# TalkingTom_FINAL9.net
KiCad netlist of a schematic drawn in EAGLE
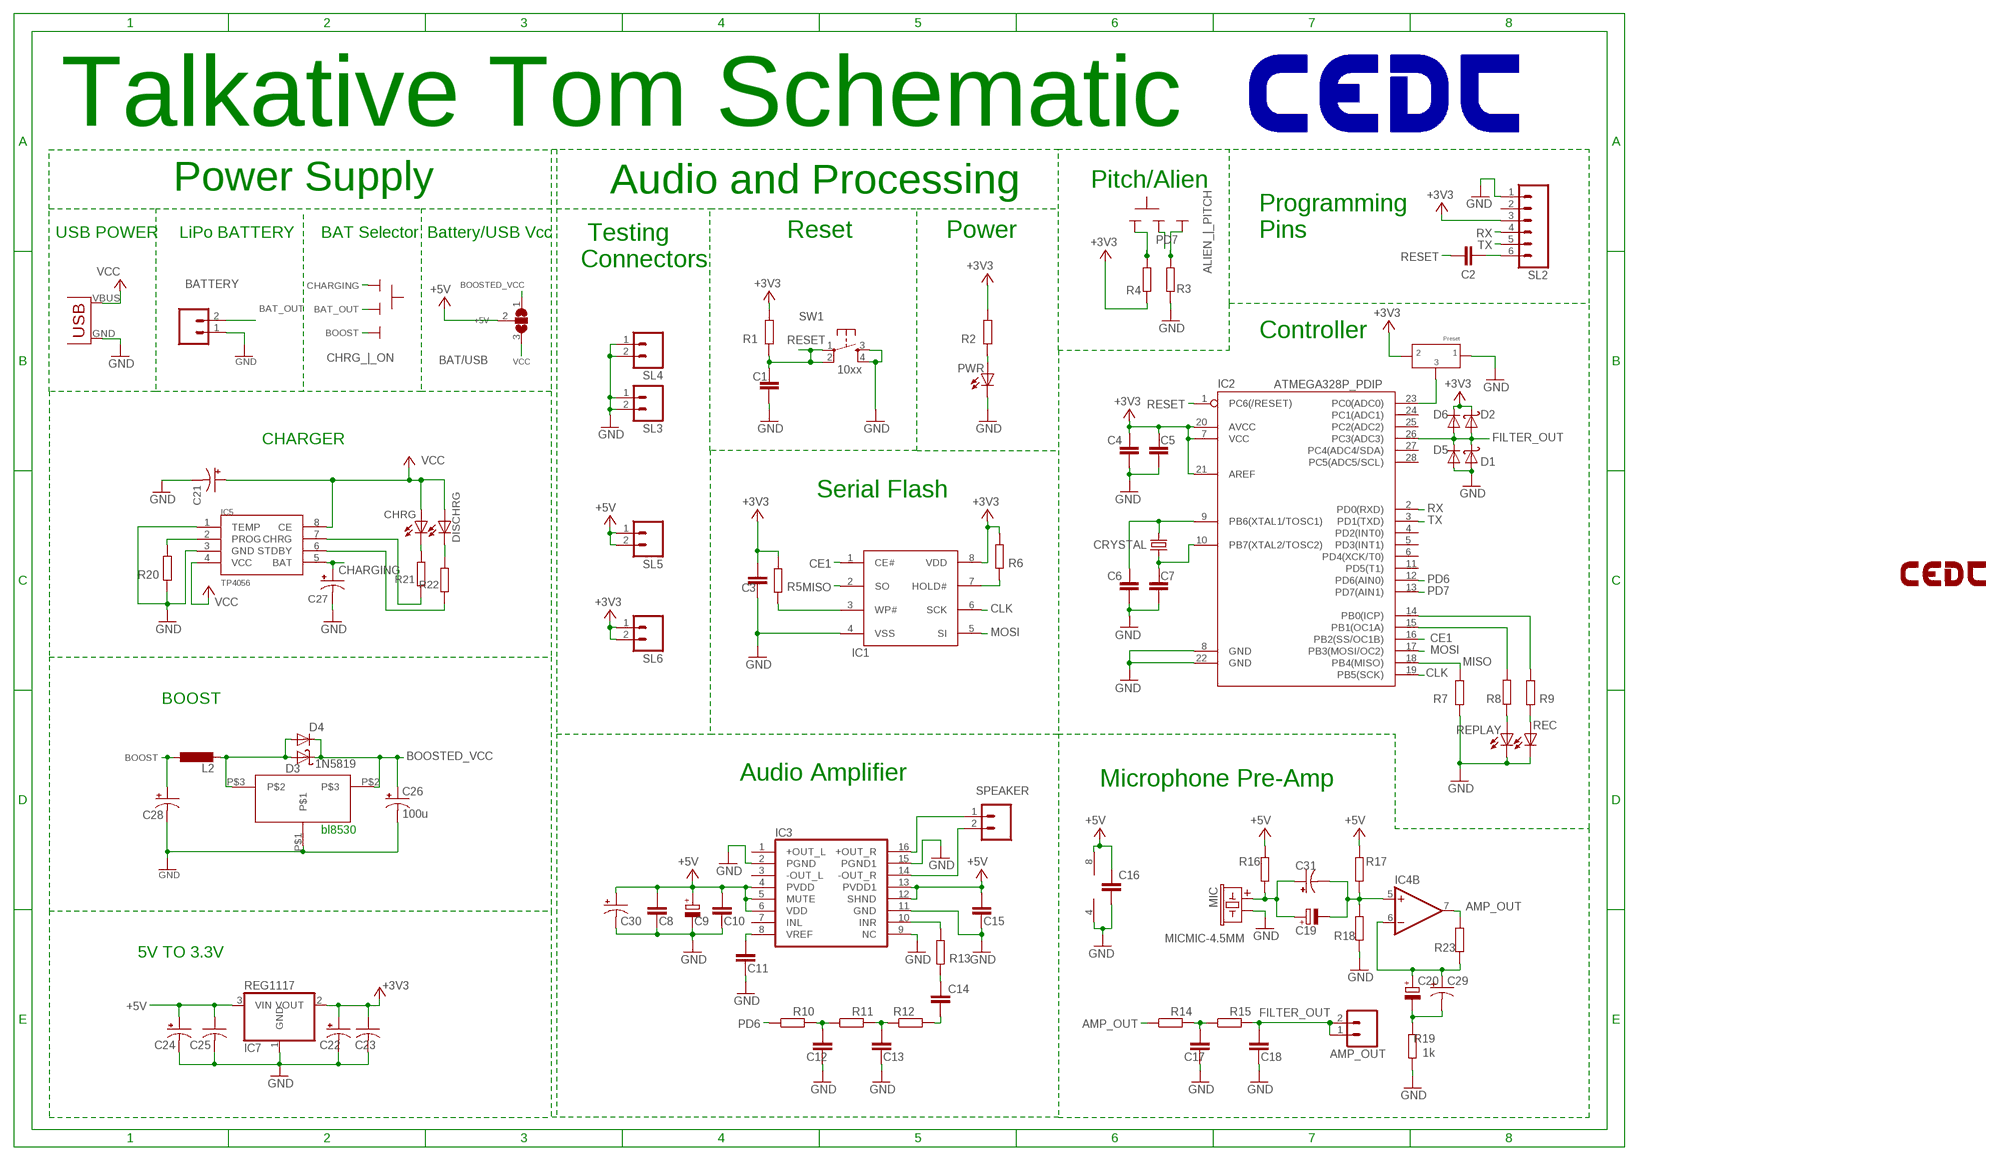
[diagram p0: schematic, sheet 1]

(export (version "E")
  (design (tool "Eeschema 10.0.6"))
  (components
    (comp (ref "ALIEN_|_PITCH")
      (value "SLIDESWITCH-BIG")
      (footprint "eagle-import:BIGSWITCH")
      (libsource (lib "eagle-import") (part "SLIDESWITCH-BIG"))
    )
    (comp (ref "AMP_OUT")
      (value "M02")
      (footprint "eagle-import:02P")
      (libsource (lib "eagle-import") (part "M02"))
    )
    (comp (ref "BAT/USB")
      (value "SJ2W")
      (footprint "eagle-import:SJ_2")
      (libsource (lib "eagle-import") (part "SJ2W"))
    )
    (comp (ref "BATTERY")
      (value "M02JST-PTH-2")
      (footprint "eagle-import:02P")
      (libsource (lib "eagle-import") (part "M02"))
    )
    (comp (ref "C1")
      (value "0.1u")
      (footprint "eagle-import:C0805")
      (libsource (lib "eagle-import") (part "rcl_C-EUC0805"))
    )
    (comp (ref "C2")
      (value "1uf")
      (footprint "eagle-import:C1206K")
      (libsource (lib "eagle-import") (part "rcl_C-EUC1206K"))
    )
    (comp (ref "C3")
      (value "0.1u")
      (footprint "eagle-import:C0805")
      (libsource (lib "eagle-import") (part "rcl_C-EUC0805"))
    )
    (comp (ref "C4")
      (value "0.1u")
      (footprint "eagle-import:C0805")
      (libsource (lib "eagle-import") (part "rcl_C-EUC0805"))
    )
    (comp (ref "C5")
      (value "0.1u")
      (footprint "eagle-import:C0805")
      (libsource (lib "eagle-import") (part "rcl_C-EUC0805"))
    )
    (comp (ref "C6")
      (value "22pf")
      (footprint "eagle-import:C0805")
      (libsource (lib "eagle-import") (part "rcl_C-EUC0805"))
    )
    (comp (ref "C7")
      (value "22pf")
      (footprint "eagle-import:C0805")
      (libsource (lib "eagle-import") (part "rcl_C-EUC0805"))
    )
    (comp (ref "C8")
      (value "1uf")
      (footprint "eagle-import:C1206")
      (libsource (lib "eagle-import") (part "rcl_C-EUC1206"))
    )
    (comp (ref "C9")
      (value "470uF")
      (footprint "eagle-import:E5-10,5")
      (libsource (lib "eagle-import") (part "resistor_CPOL-EUE5-10.5"))
    )
    (comp (ref "C10")
      (value "1uf")
      (footprint "eagle-import:C1206")
      (libsource (lib "eagle-import") (part "rcl_C-EUC1206"))
    )
    (comp (ref "C11")
      (value "0.1uf")
      (footprint "eagle-import:C1206")
      (libsource (lib "eagle-import") (part "rcl_C-EUC1206"))
    )
    (comp (ref "C12")
      (value "0.1u")
      (footprint "eagle-import:C0805")
      (libsource (lib "eagle-import") (part "C-EUC0805"))
    )
    (comp (ref "C13")
      (value "0.1uf")
      (footprint "eagle-import:C0805")
      (libsource (lib "eagle-import") (part "C-EUC0805"))
    )
    (comp (ref "C14")
      (value "0.47uF")
      (footprint "eagle-import:C0603")
      (libsource (lib "eagle-import") (part "rcl_C-EUC0603"))
    )
    (comp (ref "C15")
      (value "1uf")
      (footprint "eagle-import:C1206")
      (libsource (lib "eagle-import") (part "rcl_C-EUC1206"))
    )
    (comp (ref "C16")
      (value "0.1u")
      (footprint "eagle-import:C0805")
      (libsource (lib "eagle-import") (part "resistor_C-EUC0805"))
    )
    (comp (ref "C17")
      (value "0.1u")
      (footprint "eagle-import:C0805")
      (libsource (lib "eagle-import") (part "C-EUC0805"))
    )
    (comp (ref "C18")
      (value "0.1u")
      (footprint "eagle-import:C0805")
      (libsource (lib "eagle-import") (part "C-EUC0805"))
    )
    (comp (ref "C19")
      (value "10u")
      (footprint "eagle-import:E2,5-5")
      (libsource (lib "eagle-import") (part "CPOL-EUE2.5-5"))
    )
    (comp (ref "C20")
      (value "10u")
      (footprint "eagle-import:E2,5-5")
      (libsource (lib "eagle-import") (part "CPOL-EUE2.5-5"))
    )
    (comp (ref "C21")
      (value "10u")
      (footprint "eagle-import:C_6032-28R")
      (libsource (lib "eagle-import") (part "CEDT_JANUARY_2015_v7_CAP_POL_10V"))
    )
    (comp (ref "C22")
      (value "10u")
      (footprint "eagle-import:C_6032-28R")
      (libsource (lib "eagle-import") (part "CAP_POL_10V"))
    )
    (comp (ref "C23")
      (value "0.1u")
      (footprint "eagle-import:C0805")
      (libsource (lib "eagle-import") (part "CAP0805"))
    )
    (comp (ref "C24")
      (value "10u")
      (footprint "eagle-import:C_6032-28R")
      (libsource (lib "eagle-import") (part "CAP_POL_10V"))
    )
    (comp (ref "C25")
      (value "0.1u")
      (footprint "eagle-import:C0805")
      (libsource (lib "eagle-import") (part "CAP0805"))
    )
    (comp (ref "C26")
      (value "100u")
      (footprint "eagle-import:C_6032-28R")
      (libsource (lib "eagle-import") (part "CEDT_JANUARY_2015_v7_CAP_POL_10V"))
    )
    (comp (ref "C27")
      (value "10u")
      (footprint "eagle-import:C_6032-28R")
      (libsource (lib "eagle-import") (part "CAP_POL_10V"))
    )
    (comp (ref "C28")
      (value "10u")
      (footprint "eagle-import:C_6032-28R")
      (libsource (lib "eagle-import") (part "CAP_POL_10V"))
    )
    (comp (ref "C29")
      (value "10u")
      (footprint "eagle-import:C_6032-28R")
      (libsource (lib "eagle-import") (part "CEDT_JANUARY_2015_v7_CAP_POL_10V"))
    )
    (comp (ref "C30")
      (value "CAP_POL_10V")
      (footprint "eagle-import:C_6032-28R")
      (libsource (lib "eagle-import") (part "CEDT_SEPTEMBER_V2_CAP_POL_10V"))
    )
    (comp (ref "C31")
      (value "10u")
      (footprint "eagle-import:C_6032-28R")
      (libsource (lib "eagle-import") (part "CEDT_JANUARY_2015_v7_CAP_POL_10V"))
    )
    (comp (ref "CHRG")
      (value "LED3MM")
      (footprint "eagle-import:LED3MM")
      (libsource (lib "eagle-import") (part "adafruit_LED3MM"))
    )
    (comp (ref "CHRG_|_ON")
      (value "SLIDESWITCH-BIG")
      (footprint "eagle-import:BIGSWITCH")
      (libsource (lib "eagle-import") (part "SLIDESWITCH-BIG"))
    )
    (comp (ref "CRYSTAL")
      (value "16MHz")
      (footprint "eagle-import:HC49US")
      (libsource (lib "eagle-import") (part "CRYSTALHC49US"))
    )
    (comp (ref "D1")
      (value "1N5819")
      (footprint "eagle-import:DO41-10")
      (libsource (lib "eagle-import") (part "1N5819"))
    )
    (comp (ref "D2")
      (value "1N5819")
      (footprint "eagle-import:DO41-10")
      (libsource (lib "eagle-import") (part "1N5819"))
    )
    (comp (ref "D3")
      (value "1N5819")
      (footprint "eagle-import:DO41-10")
      (libsource (lib "eagle-import") (part "arduinodaya_v9_1N5819"))
    )
    (comp (ref "D4")
      (value "DIODE_DIODE-DO214AC")
      (footprint "eagle-import:DIODE_DO214AC")
      (libsource (lib "eagle-import") (part "DIODE_DIODE-DO214AC"))
    )
    (comp (ref "D5")
      (value "DIODE_DIODE-DO214AC")
      (footprint "eagle-import:DIODE_DO214AC")
      (libsource (lib "eagle-import") (part "DIODE_DIODE-DO214AC"))
    )
    (comp (ref "D6")
      (value "DIODE_DIODE-DO214AC")
      (footprint "eagle-import:DIODE_DO214AC")
      (libsource (lib "eagle-import") (part "DIODE_DIODE-DO214AC"))
    )
    (comp (ref "DISCHRG")
      (value "LED3MM")
      (footprint "eagle-import:LED3MM")
      (libsource (lib "eagle-import") (part "adafruit_LED3MM"))
    )
    (comp (ref "IC1")
      (value "SST25VF040B_SPI_FLASH")
      (footprint "eagle-import:SOIC08")
      (libsource (lib "eagle-import") (part "SST25VF040B_SPI_FLASH"))
    )
    (comp (ref "IC2")
      (value "ATMEGA328P_PDIP")
      (footprint "eagle-import:DIL28-3")
      (libsource (lib "eagle-import") (part "ATMEGA328P_PDIP"))
    )
    (comp (ref "IC3")
      (value "PAM8403")
      (footprint "eagle-import:SOP-16")
      (libsource (lib "eagle-import") (part "PAM8403"))
    )
    (comp (ref "IC4")
      (value "LM358N")
      (footprint "eagle-import:DIL08")
      (libsource (lib "eagle-import") (part "LM358N"))
    )
    (comp (ref "IC5")
      (value "TP4056")
      (footprint "eagle-import:SOP-8")
      (libsource (lib "eagle-import") (part "TP4056"))
    )
    (comp (ref "IC6")
      (value "BL8530_5V")
      (footprint "eagle-import:BL8530_5V")
      (libsource (lib "eagle-import") (part "BL8530_5V"))
    )
    (comp (ref "IC7")
      (value "REG1117")
      (footprint "eagle-import:SOT223")
      (libsource (lib "eagle-import") (part "REG1117"))
    )
    (comp (ref "L2")
      (value "47uH")
      (footprint "eagle-import:L5650M")
      (libsource (lib "eagle-import") (part "L-EUL5650M"))
    )
    (comp (ref "LOGO2")
      (value "LOGO-CEDTSILK-18MM")
      (footprint "eagle-import:LOGO-CEDT-SILK-18MM")
      (libsource (lib "eagle-import") (part "LOGO-CEDTSILK-18MM"))
    )
    (comp (ref "MIC")
      (value "MICMIC-4.5MM")
      (footprint "eagle-import:MIC-4.5MM")
      (libsource (lib "eagle-import") (part "MICMIC-4.5MM"))
    )
    (comp (ref "PWR")
      (value "LED3MM")
      (footprint "eagle-import:LED3MM")
      (libsource (lib "eagle-import") (part "LED3MM"))
    )
    (comp (ref "R1")
      (value "10k")
      (footprint "eagle-import:0204_7")
      (libsource (lib "eagle-import") (part "R-EU_0204/7"))
    )
    (comp (ref "R2")
      (value "1k")
      (footprint "eagle-import:0204_7")
      (libsource (lib "eagle-import") (part "R-EU_0204/7"))
    )
    (comp (ref "R3")
      (value "10k")
      (footprint "eagle-import:0204_7")
      (libsource (lib "eagle-import") (part "R-EU_0204/7"))
    )
    (comp (ref "R4")
      (value "10k")
      (footprint "eagle-import:0204_7")
      (libsource (lib "eagle-import") (part "R-EU_0204/7"))
    )
    (comp (ref "R5")
      (value "10k")
      (footprint "eagle-import:0204_7")
      (libsource (lib "eagle-import") (part "R-EU_0204/7"))
    )
    (comp (ref "R6")
      (value "10k")
      (footprint "eagle-import:0204_7")
      (libsource (lib "eagle-import") (part "R-EU_0204/7"))
    )
    (comp (ref "R7")
      (value "10k")
      (footprint "eagle-import:0204_7")
      (libsource (lib "eagle-import") (part "R-EU_0204/7"))
    )
    (comp (ref "R8")
      (value "1k")
      (footprint "eagle-import:0204_7")
      (libsource (lib "eagle-import") (part "R-EU_0204/7"))
    )
    (comp (ref "R9")
      (value "1k")
      (footprint "eagle-import:0204_7")
      (libsource (lib "eagle-import") (part "R-EU_0204/7"))
    )
    (comp (ref "R10")
      (value "330")
      (footprint "eagle-import:0204_7")
      (libsource (lib "eagle-import") (part "R-EU_0204/7"))
    )
    (comp (ref "R11")
      (value "330")
      (footprint "eagle-import:0204_7")
      (libsource (lib "eagle-import") (part "R-EU_0204/7"))
    )
    (comp (ref "R12")
      (value "R-EU_0204/7")
      (footprint "eagle-import:0204_7")
      (libsource (lib "eagle-import") (part "resistor_R-EU_0204/7"))
    )
    (comp (ref "R13")
      (value "10k")
      (footprint "eagle-import:0204_7")
      (libsource (lib "eagle-import") (part "resistor_R-EU_0204/7"))
    )
    (comp (ref "R14")
      (value "330")
      (footprint "eagle-import:0204_7")
      (libsource (lib "eagle-import") (part "R-EU_0204/7"))
    )
    (comp (ref "R15")
      (value "330")
      (footprint "eagle-import:0204_7")
      (libsource (lib "eagle-import") (part "R-EU_0204/7"))
    )
    (comp (ref "R16")
      (value "4.7k")
      (footprint "eagle-import:0204_7")
      (libsource (lib "eagle-import") (part "resistor_R-EU_0204/7"))
    )
    (comp (ref "R17")
      (value "10k")
      (footprint "eagle-import:0204_7")
      (libsource (lib "eagle-import") (part "resistor_R-EU_0204/7"))
    )
    (comp (ref "R18")
      (value "20k")
      (footprint "eagle-import:0204_7")
      (libsource (lib "eagle-import") (part "R-EU_0204/7"))
    )
    (comp (ref "R19")
      (value "1k")
      (footprint "eagle-import:0204_7")
      (libsource (lib "eagle-import") (part "resistor_R-EU_0204/7"))
    )
    (comp (ref "R20")
      (value "R-EU_0204/7")
      (footprint "eagle-import:0204_7")
      (libsource (lib "eagle-import") (part "R-EU_0204/7"))
    )
    (comp (ref "R21")
      (value "470")
      (footprint "eagle-import:0204_7")
      (libsource (lib "eagle-import") (part "R-EU_0204/7"))
    )
    (comp (ref "R22")
      (value "470")
      (footprint "eagle-import:0204_7")
      (libsource (lib "eagle-import") (part "R-EU_0204/7"))
    )
    (comp (ref "R23")
      (value "20k")
      (footprint "eagle-import:0204_7")
      (libsource (lib "eagle-import") (part "R-EU_0204/7"))
    )
    (comp (ref "REC")
      (value "LED3MM")
      (footprint "eagle-import:LED3MM")
      (libsource (lib "eagle-import") (part "LED3MM"))
    )
    (comp (ref "REPLAY")
      (value "LED3MM")
      (footprint "eagle-import:LED3MM")
      (libsource (lib "eagle-import") (part "LED3MM"))
    )
    (comp (ref "SL2")
      (value "M06")
      (footprint "eagle-import:06P")
      (libsource (lib "eagle-import") (part "M06"))
    )
    (comp (ref "SL3")
      (value "M02")
      (footprint "eagle-import:02P")
      (libsource (lib "eagle-import") (part "CEDT_JANUARY_2015_v7_M02"))
    )
    (comp (ref "SL4")
      (value "M02")
      (footprint "eagle-import:02P")
      (libsource (lib "eagle-import") (part "CEDT_JANUARY_2015_v7_M02"))
    )
    (comp (ref "SL5")
      (value "M02")
      (footprint "eagle-import:02P")
      (libsource (lib "eagle-import") (part "CEDT_JANUARY_2015_v7_M02"))
    )
    (comp (ref "SL6")
      (value "M02")
      (footprint "eagle-import:02P")
      (libsource (lib "eagle-import") (part "CEDT_JANUARY_2015_v7_M02"))
    )
    (comp (ref "SPEAKER")
      (value "M02JST-PTH-VERT")
      (footprint "eagle-import:02P")
      (libsource (lib "eagle-import") (part "M02"))
    )
    (comp (ref "SW1")
      (value "10xx")
      (footprint "eagle-import:B3F-10XX")
      (libsource (lib "eagle-import") (part "OMRON_SWITCH_10-XX"))
    )
    (comp (ref "TRIMPOT")
      (value "Preset")
      (footprint "eagle-import:PRESET-LR")
      (libsource (lib "eagle-import") (part "PRESET"))
    )
    (comp (ref "U$1")
      (value "USB(POWER)")
      (footprint "eagle-import:USB(POWER)")
      (libsource (lib "eagle-import") (part "USB(POWER)"))
    )
  )
  (nets
    (net (code "1") (name "+3V3") (class "Default")
      (node (ref "C22") (pin "+") (pinfunction "+_+") (pintype "passive"))
      (node (ref "C23") (pin "1") (pinfunction "1_1") (pintype "passive"))
      (node (ref "C3") (pin "1") (pinfunction "1_1") (pintype "passive"))
      (node (ref "C4") (pin "1") (pinfunction "1_1") (pintype "passive"))
      (node (ref "C5") (pin "1") (pinfunction "1_1") (pintype "passive"))
      (node (ref "D2") (pin "C") (pinfunction "C_C") (pintype "passive"))
      (node (ref "D6") (pin "C") (pinfunction "C_C") (pintype "passive"))
      (node (ref "IC1") (pin "8") (pinfunction "VDD_8") (pintype "passive"))
      (node (ref "IC2") (pin "20") (pinfunction "AVCC_20") (pintype "bidirectional"))
      (node (ref "IC2") (pin "21") (pinfunction "AREF_21") (pintype "bidirectional"))
      (node (ref "IC2") (pin "7") (pinfunction "VCC_7") (pintype "bidirectional"))
      (node (ref "IC7") (pin "2") (pinfunction "VOUT_2") (pintype "output"))
      (node (ref "R1") (pin "2") (pinfunction "2_2") (pintype "passive"))
      (node (ref "R2") (pin "2") (pinfunction "2_2") (pintype "passive"))
      (node (ref "R4") (pin "2") (pinfunction "2_2") (pintype "passive"))
      (node (ref "R5") (pin "1") (pinfunction "1_1") (pintype "passive"))
      (node (ref "R6") (pin "2") (pinfunction "2_2") (pintype "passive"))
      (node (ref "SL2") (pin "3") (pinfunction "3_3") (pintype "passive"))
      (node (ref "SL6") (pin "1") (pinfunction "1_1") (pintype "passive"))
      (node (ref "SL6") (pin "2") (pinfunction "2_2") (pintype "passive"))
      (node (ref "TRIMPOT") (pin "P$2") (pinfunction "2_P$2") (pintype "passive"))
    )
    (net (code "2") (name "+5V") (class "Default")
      (node (ref "BAT/USB") (pin "2") (pinfunction "2_2") (pintype "passive"))
      (node (ref "C10") (pin "2") (pinfunction "2_2") (pintype "passive"))
      (node (ref "C15") (pin "2") (pinfunction "2_2") (pintype "passive"))
      (node (ref "C16") (pin "1") (pinfunction "1_1") (pintype "passive"))
      (node (ref "C24") (pin "+") (pinfunction "+_+") (pintype "passive"))
      (node (ref "C25") (pin "1") (pinfunction "1_1") (pintype "passive"))
      (node (ref "C30") (pin "+") (pinfunction "+_+") (pintype "passive"))
      (node (ref "C8") (pin "1") (pinfunction "1_1") (pintype "passive"))
      (node (ref "C9") (pin "+") (pinfunction "+_+") (pintype "passive"))
      (node (ref "IC3") (pin "12") (pinfunction "SHND_12") (pintype "output"))
      (node (ref "IC3") (pin "13") (pinfunction "PVDD1_13") (pintype "output"))
      (node (ref "IC3") (pin "4") (pinfunction "PVDD_4") (pintype "input"))
      (node (ref "IC3") (pin "5") (pinfunction "MUTE_5") (pintype "input"))
      (node (ref "IC3") (pin "6") (pinfunction "VDD_6") (pintype "input"))
      (node (ref "IC4") (pin "8") (pinfunction "V+_8") (pintype "power_in"))
      (node (ref "IC7") (pin "3") (pinfunction "VIN_3") (pintype "input"))
      (node (ref "R16") (pin "2") (pinfunction "2_2") (pintype "passive"))
      (node (ref "R17") (pin "2") (pinfunction "2_2") (pintype "passive"))
      (node (ref "SL5") (pin "1") (pinfunction "1_1") (pintype "passive"))
      (node (ref "SL5") (pin "2") (pinfunction "2_2") (pintype "passive"))
    )
    (net (code "3") (name "/AMP_OUT") (class "Default")
      (node (ref "IC4") (pin "7") (pinfunction "OUT_7") (pintype "output"))
      (node (ref "R14") (pin "1") (pinfunction "1_1") (pintype "passive"))
      (node (ref "R23") (pin "2") (pinfunction "2_2") (pintype "passive"))
    )
    (net (code "4") (name "/BAT_OUT") (class "Default")
      (node (ref "BATTERY") (pin "2") (pinfunction "2_2") (pintype "passive"))
      (node (ref "CHRG_|_ON") (pin "2") (pinfunction "2_2") (pintype "bidirectional"))
    )
    (net (code "5") (name "/BOOST") (class "Default")
      (node (ref "C28") (pin "+") (pinfunction "+_+") (pintype "passive"))
      (node (ref "CHRG_|_ON") (pin "3") (pinfunction "3_3") (pintype "bidirectional"))
      (node (ref "L2") (pin "1") (pinfunction "1_1") (pintype "passive"))
    )
    (net (code "6") (name "/BOOSTED_VCC") (class "Default")
      (node (ref "BAT/USB") (pin "1") (pinfunction "1_1") (pintype "passive"))
      (node (ref "C26") (pin "+") (pinfunction "+_+") (pintype "passive"))
      (node (ref "D3") (pin "C") (pinfunction "C_C") (pintype "passive"))
      (node (ref "D4") (pin "C") (pinfunction "C_C") (pintype "passive"))
      (node (ref "IC6") (pin "P$2") (pinfunction "P$3_P$2") (pintype "bidirectional"))
    )
    (net (code "7") (name "/CE1") (class "Default")
      (node (ref "IC1") (pin "1") (pinfunction "CE#_1") (pintype "passive"))
      (node (ref "IC2") (pin "16") (pinfunction "PB2(SS/OC1B)_16") (pintype "bidirectional"))
    )
    (net (code "8") (name "/CHARGING") (class "Default")
      (node (ref "C27") (pin "+") (pinfunction "+_+") (pintype "passive"))
      (node (ref "CHRG_|_ON") (pin "1") (pinfunction "1_1") (pintype "bidirectional"))
      (node (ref "IC5") (pin "5") (pinfunction "BAT_5") (pintype "bidirectional"))
    )
    (net (code "9") (name "/CLK") (class "Default")
      (node (ref "IC1") (pin "6") (pinfunction "SCK_6") (pintype "passive"))
      (node (ref "IC2") (pin "19") (pinfunction "PB5(SCK)_19") (pintype "bidirectional"))
    )
    (net (code "10") (name "/FILTER_OUT") (class "Default")
      (node (ref "AMP_OUT") (pin "1") (pinfunction "1_1") (pintype "passive"))
      (node (ref "AMP_OUT") (pin "2") (pinfunction "2_2") (pintype "passive"))
      (node (ref "C18") (pin "1") (pinfunction "1_1") (pintype "passive"))
      (node (ref "D1") (pin "C") (pinfunction "C_C") (pintype "passive"))
      (node (ref "D2") (pin "A") (pinfunction "A_A") (pintype "passive"))
      (node (ref "D5") (pin "C") (pinfunction "C_C") (pintype "passive"))
      (node (ref "D6") (pin "A") (pinfunction "A_A") (pintype "passive"))
      (node (ref "IC2") (pin "26") (pinfunction "PC3(ADC3)_26") (pintype "bidirectional"))
      (node (ref "R15") (pin "2") (pinfunction "2_2") (pintype "passive"))
    )
    (net (code "11") (name "/MISO") (class "Default")
      (node (ref "IC1") (pin "2") (pinfunction "SO_2") (pintype "passive"))
      (node (ref "IC2") (pin "18") (pinfunction "PB4(MISO)_18") (pintype "bidirectional"))
      (node (ref "R7") (pin "1") (pinfunction "1_1") (pintype "passive"))
    )
    (net (code "12") (name "/MOSI") (class "Default")
      (node (ref "IC1") (pin "5") (pinfunction "SI_5") (pintype "passive"))
      (node (ref "IC2") (pin "17") (pinfunction "PB3(MOSI/OC2)_17") (pintype "bidirectional"))
    )
    (net (code "13") (name "/PD6") (class "Default")
      (node (ref "IC2") (pin "12") (pinfunction "PD6(AIN0)_12") (pintype "bidirectional"))
      (node (ref "R10") (pin "1") (pinfunction "1_1") (pintype "passive"))
    )
    (net (code "14") (name "/PD7") (class "Default")
      (node (ref "ALIEN_|_PITCH") (pin "2") (pinfunction "2_2") (pintype "bidirectional"))
      (node (ref "IC2") (pin "13") (pinfunction "PD7(AIN1)_13") (pintype "bidirectional"))
    )
    (net (code "15") (name "/RESET") (class "Default")
      (node (ref "C1") (pin "1") (pinfunction "1_1") (pintype "passive"))
      (node (ref "C2") (pin "2") (pinfunction "2_2") (pintype "passive"))
      (node (ref "IC2") (pin "1") (pinfunction "PC6(/RESET)_1") (pintype "bidirectional"))
      (node (ref "R1") (pin "1") (pinfunction "1_1") (pintype "passive"))
      (node (ref "SW1") (pin "1") (pinfunction "P_1") (pintype "passive"))
      (node (ref "SW1") (pin "2") (pinfunction "P1_2") (pintype "passive"))
    )
    (net (code "16") (name "/RX") (class "Default")
      (node (ref "IC2") (pin "2") (pinfunction "PD0(RXD)_2") (pintype "bidirectional"))
      (node (ref "SL2") (pin "4") (pinfunction "4_4") (pintype "passive"))
    )
    (net (code "17") (name "/TX") (class "Default")
      (node (ref "IC2") (pin "3") (pinfunction "PD1(TXD)_3") (pintype "bidirectional"))
      (node (ref "SL2") (pin "5") (pinfunction "5_5") (pintype "passive"))
    )
    (net (code "18") (name "GND") (class "Default")
      (node (ref "BATTERY") (pin "1") (pinfunction "1_1") (pintype "passive"))
      (node (ref "C1") (pin "2") (pinfunction "2_2") (pintype "passive"))
      (node (ref "C10") (pin "1") (pinfunction "1_1") (pintype "passive"))
      (node (ref "C11") (pin "2") (pinfunction "2_2") (pintype "passive"))
      (node (ref "C12") (pin "2") (pinfunction "2_2") (pintype "passive"))
      (node (ref "C13") (pin "2") (pinfunction "2_2") (pintype "passive"))
      (node (ref "C15") (pin "1") (pinfunction "1_1") (pintype "passive"))
      (node (ref "C16") (pin "2") (pinfunction "2_2") (pintype "passive"))
      (node (ref "C17") (pin "2") (pinfunction "2_2") (pintype "passive"))
      (node (ref "C18") (pin "2") (pinfunction "2_2") (pintype "passive"))
      (node (ref "C21") (pin "-") (pinfunction "-_-") (pintype "passive"))
      (node (ref "C22") (pin "-") (pinfunction "-_-") (pintype "passive"))
      (node (ref "C23") (pin "2") (pinfunction "2_2") (pintype "passive"))
      (node (ref "C24") (pin "-") (pinfunction "-_-") (pintype "passive"))
      (node (ref "C25") (pin "2") (pinfunction "2_2") (pintype "passive"))
      (node (ref "C26") (pin "-") (pinfunction "-_-") (pintype "passive"))
      (node (ref "C27") (pin "-") (pinfunction "-_-") (pintype "passive"))
      (node (ref "C28") (pin "-") (pinfunction "-_-") (pintype "passive"))
      (node (ref "C3") (pin "2") (pinfunction "2_2") (pintype "passive"))
      (node (ref "C30") (pin "-") (pinfunction "-_-") (pintype "passive"))
      (node (ref "C4") (pin "2") (pinfunction "2_2") (pintype "passive"))
      (node (ref "C5") (pin "2") (pinfunction "2_2") (pintype "passive"))
      (node (ref "C6") (pin "2") (pinfunction "2_2") (pintype "passive"))
      (node (ref "C7") (pin "2") (pinfunction "2_2") (pintype "passive"))
      (node (ref "C8") (pin "2") (pinfunction "2_2") (pintype "passive"))
      (node (ref "C9") (pin "-") (pinfunction "-_-") (pintype "passive"))
      (node (ref "D1") (pin "A") (pinfunction "A_A") (pintype "passive"))
      (node (ref "D5") (pin "A") (pinfunction "A_A") (pintype "passive"))
      (node (ref "IC1") (pin "4") (pinfunction "VSS_4") (pintype "passive"))
      (node (ref "IC2") (pin "22") (pinfunction "GND_22") (pintype "bidirectional"))
      (node (ref "IC2") (pin "8") (pinfunction "GND_8") (pintype "bidirectional"))
      (node (ref "IC3") (pin "11") (pinfunction "GND_11") (pintype "output"))
      (node (ref "IC3") (pin "15") (pinfunction "PGND1_15") (pintype "output"))
      (node (ref "IC3") (pin "2") (pinfunction "PGND_2") (pintype "input"))
      (node (ref "IC3") (pin "9") (pinfunction "NC_9") (pintype "output"))
      (node (ref "IC4") (pin "4") (pinfunction "V-_4") (pintype "power_in"))
      (node (ref "IC5") (pin "1") (pinfunction "TEMP_1") (pintype "bidirectional"))
      (node (ref "IC5") (pin "3") (pinfunction "GND_3") (pintype "bidirectional"))
      (node (ref "IC6") (pin "P$1") (pinfunction "P$1_P$1") (pintype "bidirectional"))
      (node (ref "IC7") (pin "1") (pinfunction "GND_1") (pintype "power_in"))
      (node (ref "MIC") (pin "+") (pinfunction "2_+") (pintype "passive"))
      (node (ref "PWR") (pin "K") (pinfunction "C_K") (pintype "passive"))
      (node (ref "R18") (pin "1") (pinfunction "1_1") (pintype "passive"))
      (node (ref "R19") (pin "1") (pinfunction "1_1") (pintype "passive"))
      (node (ref "R20") (pin "1") (pinfunction "1_1") (pintype "passive"))
      (node (ref "R3") (pin "2") (pinfunction "2_2") (pintype "passive"))
      (node (ref "R7") (pin "2") (pinfunction "2_2") (pintype "passive"))
      (node (ref "REC") (pin "K") (pinfunction "C_K") (pintype "passive"))
      (node (ref "REPLAY") (pin "K") (pinfunction "C_K") (pintype "passive"))
      (node (ref "SL2") (pin "1") (pinfunction "1_1") (pintype "passive"))
      (node (ref "SL3") (pin "1") (pinfunction "1_1") (pintype "passive"))
      (node (ref "SL3") (pin "2") (pinfunction "2_2") (pintype "passive"))
      (node (ref "SL4") (pin "1") (pinfunction "1_1") (pintype "passive"))
      (node (ref "SL4") (pin "2") (pinfunction "2_2") (pintype "passive"))
      (node (ref "SW1") (pin "3") (pinfunction "S_3") (pintype "passive"))
      (node (ref "SW1") (pin "4") (pinfunction "S1_4") (pintype "passive"))
      (node (ref "TRIMPOT") (pin "P$1") (pinfunction "1_P$1") (pintype "passive"))
      (node (ref "U$1") (pin "GND") (pinfunction "GND_GND") (pintype "power_in"))
    )
    (net (code "19") (name "Net-(ALIEN_|_PITCH-Pad1)") (class "Default")
      (node (ref "ALIEN_|_PITCH") (pin "1") (pinfunction "1_1") (pintype "bidirectional"))
      (node (ref "R4") (pin "1") (pinfunction "1_1") (pintype "passive"))
    )
    (net (code "20") (name "Net-(ALIEN_|_PITCH-Pad3)") (class "Default")
      (node (ref "ALIEN_|_PITCH") (pin "3") (pinfunction "3_3") (pintype "bidirectional"))
      (node (ref "R3") (pin "1") (pinfunction "1_1") (pintype "passive"))
    )
    (net (code "21") (name "Net-(C2-Pad1)") (class "Default")
      (node (ref "C2") (pin "1") (pinfunction "1_1") (pintype "passive"))
      (node (ref "SL2") (pin "6") (pinfunction "6_6") (pintype "passive"))
    )
    (net (code "22") (name "Net-(C12-Pad1)") (class "Default")
      (node (ref "C12") (pin "1") (pinfunction "1_1") (pintype "passive"))
      (node (ref "R10") (pin "2") (pinfunction "2_2") (pintype "passive"))
      (node (ref "R11") (pin "1") (pinfunction "1_1") (pintype "passive"))
    )
    (net (code "23") (name "Net-(C13-Pad1)") (class "Default")
      (node (ref "C13") (pin "1") (pinfunction "1_1") (pintype "passive"))
      (node (ref "R11") (pin "2") (pinfunction "2_2") (pintype "passive"))
      (node (ref "R12") (pin "1") (pinfunction "1_1") (pintype "passive"))
    )
    (net (code "24") (name "Net-(C14-Pad1)") (class "Default")
      (node (ref "C14") (pin "1") (pinfunction "1_1") (pintype "passive"))
      (node (ref "R12") (pin "2") (pinfunction "2_2") (pintype "passive"))
    )
    (net (code "25") (name "Net-(C14-Pad2)") (class "Default")
      (node (ref "C14") (pin "2") (pinfunction "2_2") (pintype "passive"))
      (node (ref "R13") (pin "2") (pinfunction "2_2") (pintype "passive"))
    )
    (net (code "26") (name "Net-(C17-Pad1)") (class "Default")
      (node (ref "C17") (pin "1") (pinfunction "1_1") (pintype "passive"))
      (node (ref "R14") (pin "2") (pinfunction "2_2") (pintype "passive"))
      (node (ref "R15") (pin "1") (pinfunction "1_1") (pintype "passive"))
    )
    (net (code "27") (name "Net-(C20-Pad-)") (class "Default")
      (node (ref "C20") (pin "-") (pinfunction "-_-") (pintype "passive"))
      (node (ref "C29") (pin "-") (pinfunction "-_-") (pintype "passive"))
      (node (ref "R19") (pin "2") (pinfunction "2_2") (pintype "passive"))
    )
    (net (code "28") (name "Net-(CHRG-C)") (class "Default")
      (node (ref "CHRG") (pin "K") (pinfunction "C_K") (pintype "passive"))
      (node (ref "R21") (pin "2") (pinfunction "2_2") (pintype "passive"))
    )
    (net (code "29") (name "Net-(DISCHRG-C)") (class "Default")
      (node (ref "DISCHRG") (pin "K") (pinfunction "C_K") (pintype "passive"))
      (node (ref "R22") (pin "2") (pinfunction "2_2") (pintype "passive"))
    )
    (net (code "30") (name "Net-(IC1-HOLD#)") (class "Default")
      (node (ref "IC1") (pin "7") (pinfunction "HOLD#_7") (pintype "passive"))
      (node (ref "R6") (pin "1") (pinfunction "1_1") (pintype "passive"))
    )
    (net (code "31") (name "Net-(IC1-WP#)") (class "Default")
      (node (ref "IC1") (pin "3") (pinfunction "WP#_3") (pintype "passive"))
      (node (ref "R5") (pin "2") (pinfunction "2_2") (pintype "passive"))
    )
    (net (code "32") (name "Net-(IC2-PB0(ICP))") (class "Default")
      (node (ref "IC2") (pin "14") (pinfunction "PB0(ICP)_14") (pintype "bidirectional"))
      (node (ref "R9") (pin "1") (pinfunction "1_1") (pintype "passive"))
    )
    (net (code "33") (name "Net-(IC2-PB1(OC1A))") (class "Default")
      (node (ref "IC2") (pin "15") (pinfunction "PB1(OC1A)_15") (pintype "bidirectional"))
      (node (ref "R8") (pin "2") (pinfunction "2_2") (pintype "passive"))
    )
    (net (code "34") (name "Net-(IC2-PB6(XTAL1{slash}TOSC1))") (class "Default")
      (node (ref "C6") (pin "1") (pinfunction "1_1") (pintype "passive"))
      (node (ref "CRYSTAL") (pin "2") (pinfunction "2_2") (pintype "passive"))
      (node (ref "IC2") (pin "9") (pinfunction "PB6(XTAL1/TOSC1)_9") (pintype "bidirectional"))
    )
    (net (code "35") (name "Net-(IC2-PB7(XTAL2{slash}TOSC2))") (class "Default")
      (node (ref "C7") (pin "1") (pinfunction "1_1") (pintype "passive"))
      (node (ref "CRYSTAL") (pin "1") (pinfunction "1_1") (pintype "passive"))
      (node (ref "IC2") (pin "10") (pinfunction "PB7(XTAL2/TOSC2)_10") (pintype "bidirectional"))
    )
    (net (code "36") (name "Net-(IC2-PC0(ADC0))") (class "Default")
      (node (ref "IC2") (pin "23") (pinfunction "PC0(ADC0)_23") (pintype "bidirectional"))
      (node (ref "TRIMPOT") (pin "P$3") (pinfunction "3_P$3") (pintype "passive"))
    )
    (net (code "37") (name "Net-(IC3-+OUT_R)") (class "Default")
      (node (ref "IC3") (pin "16") (pinfunction "+OUT_R_16") (pintype "output"))
      (node (ref "SPEAKER") (pin "1") (pinfunction "1_1") (pintype "passive"))
    )
    (net (code "38") (name "Net-(IC3--OUT_R)") (class "Default")
      (node (ref "IC3") (pin "14") (pinfunction "-OUT_R_14") (pintype "output"))
      (node (ref "SPEAKER") (pin "2") (pinfunction "2_2") (pintype "passive"))
    )
    (net (code "39") (name "Net-(IC3-INR)") (class "Default")
      (node (ref "IC3") (pin "10") (pinfunction "INR_10") (pintype "output"))
      (node (ref "R13") (pin "1") (pinfunction "1_1") (pintype "passive"))
    )
    (net (code "40") (name "Net-(IC3-VREF)") (class "Default")
      (node (ref "C11") (pin "1") (pinfunction "1_1") (pintype "passive"))
      (node (ref "IC3") (pin "8") (pinfunction "VREF_8") (pintype "input"))
    )
    (net (code "41") (name "Net-(IC4B-+IN)") (class "Default")
      (node (ref "C19") (pin "-") (pinfunction "-_-") (pintype "passive"))
      (node (ref "C31") (pin "-") (pinfunction "-_-") (pintype "passive"))
      (node (ref "IC4") (pin "5") (pinfunction "+IN_5") (pintype "input"))
      (node (ref "R17") (pin "1") (pinfunction "1_1") (pintype "passive"))
      (node (ref "R18") (pin "2") (pinfunction "2_2") (pintype "passive"))
    )
    (net (code "42") (name "Net-(IC4B--IN)") (class "Default")
      (node (ref "C20") (pin "+") (pinfunction "+_+") (pintype "passive"))
      (node (ref "C29") (pin "+") (pinfunction "+_+") (pintype "passive"))
      (node (ref "IC4") (pin "6") (pinfunction "-IN_6") (pintype "input"))
      (node (ref "R23") (pin "1") (pinfunction "1_1") (pintype "passive"))
    )
    (net (code "43") (name "Net-(IC5-CHRG)") (class "Default")
      (node (ref "IC5") (pin "7") (pinfunction "CHRG_7") (pintype "bidirectional"))
      (node (ref "R21") (pin "1") (pinfunction "1_1") (pintype "passive"))
    )
    (net (code "44") (name "Net-(IC5-PROG)") (class "Default")
      (node (ref "IC5") (pin "2") (pinfunction "PROG_2") (pintype "bidirectional"))
      (node (ref "R20") (pin "2") (pinfunction "2_2") (pintype "passive"))
    )
    (net (code "45") (name "Net-(IC5-STDBY)") (class "Default")
      (node (ref "IC5") (pin "6") (pinfunction "STDBY_6") (pintype "bidirectional"))
      (node (ref "R22") (pin "1") (pinfunction "1_1") (pintype "passive"))
    )
    (net (code "46") (name "Net-(IC6-P$2)") (class "Default")
      (node (ref "D3") (pin "A") (pinfunction "A_A") (pintype "passive"))
      (node (ref "D4") (pin "A") (pinfunction "A_A") (pintype "passive"))
      (node (ref "IC6") (pin "P$3") (pinfunction "P$2_P$3") (pintype "bidirectional"))
      (node (ref "L2") (pin "2") (pinfunction "2_2") (pintype "passive"))
    )
    (net (code "47") (name "Net-(MIC-1)") (class "Default")
      (node (ref "C19") (pin "+") (pinfunction "+_+") (pintype "passive"))
      (node (ref "C31") (pin "+") (pinfunction "+_+") (pintype "passive"))
      (node (ref "MIC") (pin "-") (pinfunction "1_-") (pintype "passive"))
      (node (ref "R16") (pin "1") (pinfunction "1_1") (pintype "passive"))
    )
    (net (code "48") (name "Net-(PWR-PadA)") (class "Default")
      (node (ref "PWR") (pin "A") (pinfunction "A_A") (pintype "passive"))
      (node (ref "R2") (pin "1") (pinfunction "1_1") (pintype "passive"))
    )
    (net (code "49") (name "Net-(R8-Pad1)") (class "Default")
      (node (ref "R8") (pin "1") (pinfunction "1_1") (pintype "passive"))
      (node (ref "REPLAY") (pin "A") (pinfunction "A_A") (pintype "passive"))
    )
    (net (code "50") (name "Net-(R9-Pad2)") (class "Default")
      (node (ref "R9") (pin "2") (pinfunction "2_2") (pintype "passive"))
      (node (ref "REC") (pin "A") (pinfunction "A_A") (pintype "passive"))
    )
    (net (code "51") (name "VCC") (class "Default")
      (node (ref "BAT/USB") (pin "3") (pinfunction "3_3") (pintype "passive"))
      (node (ref "C21") (pin "+") (pinfunction "+_+") (pintype "passive"))
      (node (ref "CHRG") (pin "A") (pinfunction "A_A") (pintype "passive"))
      (node (ref "DISCHRG") (pin "A") (pinfunction "A_A") (pintype "passive"))
      (node (ref "IC5") (pin "4") (pinfunction "VCC_4") (pintype "bidirectional"))
      (node (ref "IC5") (pin "8") (pinfunction "CE_8") (pintype "bidirectional"))
      (node (ref "U$1") (pin "VBUS") (pinfunction "VCC_VBUS") (pintype "power_in"))
    )
    (net (code "52") (name "unconnected-(IC2-PC1(ADC1)-Pad24)") (class "Default")
      (node (ref "IC2") (pin "24") (pinfunction "PC1(ADC1)_24") (pintype "bidirectional"))
    )
    (net (code "53") (name "unconnected-(IC2-PC2(ADC2)-Pad25)") (class "Default")
      (node (ref "IC2") (pin "25") (pinfunction "PC2(ADC2)_25") (pintype "bidirectional"))
    )
    (net (code "54") (name "unconnected-(IC2-PC4(ADC4{slash}SDA)-Pad27)") (class "Default")
      (node (ref "IC2") (pin "27") (pinfunction "PC4(ADC4/SDA)_27") (pintype "bidirectional"))
    )
    (net (code "55") (name "unconnected-(IC2-PC5(ADC5{slash}SCL)-Pad28)") (class "Default")
      (node (ref "IC2") (pin "28") (pinfunction "PC5(ADC5/SCL)_28") (pintype "bidirectional"))
    )
    (net (code "56") (name "unconnected-(IC2-PD2(INT0)-Pad4)") (class "Default")
      (node (ref "IC2") (pin "4") (pinfunction "PD2(INT0)_4") (pintype "bidirectional"))
    )
    (net (code "57") (name "unconnected-(IC2-PD3(INT1)-Pad5)") (class "Default")
      (node (ref "IC2") (pin "5") (pinfunction "PD3(INT1)_5") (pintype "bidirectional"))
    )
    (net (code "58") (name "unconnected-(IC2-PD4(XCK{slash}T0)-Pad6)") (class "Default")
      (node (ref "IC2") (pin "6") (pinfunction "PD4(XCK/T0)_6") (pintype "bidirectional"))
    )
    (net (code "59") (name "unconnected-(IC2-PD5(T1)-Pad11)") (class "Default")
      (node (ref "IC2") (pin "11") (pinfunction "PD5(T1)_11") (pintype "bidirectional"))
    )
    (net (code "60") (name "unconnected-(IC3-+OUT_L-Pad1)") (class "Default")
      (node (ref "IC3") (pin "1") (pinfunction "+OUT_L_1") (pintype "input"))
    )
    (net (code "61") (name "unconnected-(IC3--OUT_L-Pad3)") (class "Default")
      (node (ref "IC3") (pin "3") (pinfunction "-OUT_L_3") (pintype "input"))
    )
    (net (code "62") (name "unconnected-(IC3-INL-Pad7)") (class "Default")
      (node (ref "IC3") (pin "7") (pinfunction "INL_7") (pintype "input"))
    )
    (net (code "63") (name "unconnected-(SL2-Pad2)") (class "Default")
      (node (ref "SL2") (pin "2") (pinfunction "2_2") (pintype "passive"))
    )
  )
)
